# stamp-fixed-mk-4_0.net
KiCad netlist of a schematic drawn in EAGLE
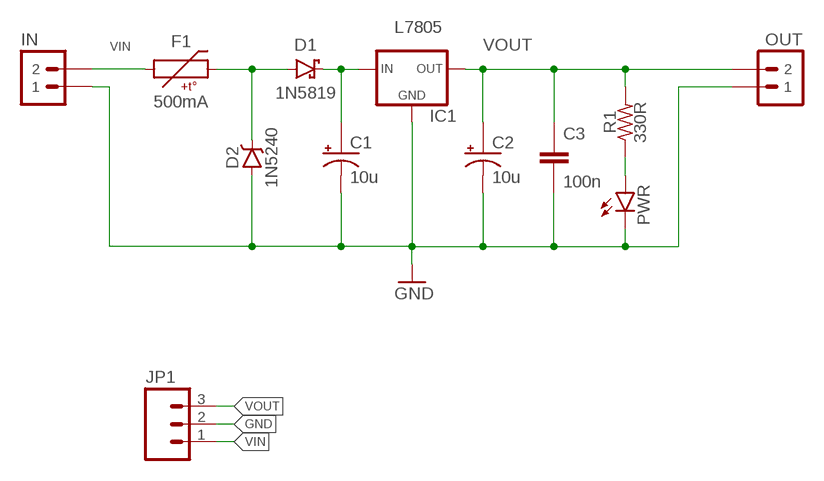
[diagram p0: schematic, sheet 1]

(export (version "E")
  (design (tool "Eeschema 10.0.6"))
  (components
    (comp (ref "C1")
      (value "10u")
      (footprint "eagle-import:E2,5-5")
      (libsource (lib "eagle-import") (part "CAPACITOR-POLARIZEDE2.5-5"))
    )
    (comp (ref "C2")
      (value "10u")
      (footprint "eagle-import:E2,5-5")
      (libsource (lib "eagle-import") (part "CAPACITOR-POLARIZEDE2.5-5"))
    )
    (comp (ref "C3")
      (value "100n")
      (footprint "eagle-import:C025-024X044")
      (libsource (lib "eagle-import") (part "CAPACITOR-CERAMIC025-024X044"))
    )
    (comp (ref "D1")
      (value "1N5819")
      (footprint "eagle-import:DIODE-SCHOTTKY-10.16MM")
      (libsource (lib "eagle-import") (part "DIODE-SCHOTTKYPTH-10.16MM"))
    )
    (comp (ref "D2")
      (value "1N5240")
      (footprint "eagle-import:DIODE-ZENNER-10.16MM")
      (libsource (lib "eagle-import") (part "DIODE-ZENER10.16MM-PTH"))
    )
    (comp (ref "F1")
      (value "500mA")
      (footprint "eagle-import:PTC-PTH-5.08MM")
      (libsource (lib "eagle-import") (part "PTCPTH-5.08MM"))
    )
    (comp (ref "IC1")
      (value "L7805")
      (footprint "eagle-import:TO220-IGO-THERMPAD")
      (libsource (lib "eagle-import") (part "V_REG_78XXTO-220-THERMPAD"))
    )
    (comp (ref "IN")
      (value "M02PTH-CENTERED-R+")
      (footprint "eagle-import:1X02-CENTER-R+")
      (libsource (lib "eagle-import") (part "M02PTH-CENTERED-R+"))
    )
    (comp (ref "JP1")
      (value "M03PTH-CENTERED")
      (footprint "eagle-import:1X03-CENTERED")
      (libsource (lib "eagle-import") (part "M03PTH-CENTERED"))
    )
    (comp (ref "OUT")
      (value "M02PTH-CENTERED-R+")
      (footprint "eagle-import:1X02-CENTER-R+")
      (libsource (lib "eagle-import") (part "M02PTH-CENTERED-R+"))
    )
    (comp (ref "PWR")
      (value "LED3MM-LESS")
      (footprint "eagle-import:LED3MM-LESSSILK")
      (libsource (lib "eagle-import") (part "LED3MM-LESS"))
    )
    (comp (ref "R1")
      (value "330R")
      (footprint "eagle-import:RESISTOR-AXIAL-PTH-5.08MM")
      (libsource (lib "eagle-import") (part "RESISTORPTH-AXIAL-5.08MM"))
    )
  )
  (nets
    (net (code "1") (name "GND") (class "Default")
      (node (ref "C1") (pin "-") (pinfunction "-_-") (pintype "passive"))
      (node (ref "C2") (pin "-") (pinfunction "-_-") (pintype "passive"))
      (node (ref "C3") (pin "2") (pinfunction "2_2") (pintype "passive"))
      (node (ref "D2") (pin "A") (pinfunction "A_A") (pintype "passive"))
      (node (ref "IC1") (pin "4") (pinfunction "GND_4") (pintype "bidirectional"))
      (node (ref "IC1") (pin "GND") (pinfunction "GND_GND") (pintype "bidirectional"))
      (node (ref "IN") (pin "1") (pinfunction "1_1") (pintype "passive"))
      (node (ref "JP1") (pin "2") (pinfunction "2_2") (pintype "passive"))
      (node (ref "OUT") (pin "1") (pinfunction "1_1") (pintype "passive"))
      (node (ref "PWR") (pin "K") (pinfunction "C_K") (pintype "passive"))
    )
    (net (code "2") (name "Net-(C1-Pad+)") (class "Default")
      (node (ref "C1") (pin "+") (pinfunction "+_+") (pintype "passive"))
      (node (ref "D1") (pin "C") (pinfunction "C_C") (pintype "passive"))
      (node (ref "IC1") (pin "IN") (pinfunction "IN_IN") (pintype "bidirectional"))
    )
    (net (code "3") (name "Net-(D2-C)") (class "Default")
      (node (ref "D1") (pin "A") (pinfunction "A_A") (pintype "passive"))
      (node (ref "D2") (pin "K") (pinfunction "C_K") (pintype "passive"))
      (node (ref "F1") (pin "P$2") (pinfunction "2_P$2") (pintype "passive"))
    )
    (net (code "4") (name "Net-(R1-1)") (class "Default")
      (node (ref "PWR") (pin "A") (pinfunction "A_A") (pintype "passive"))
      (node (ref "R1") (pin "P$1") (pinfunction "1_P$1") (pintype "passive"))
    )
    (net (code "5") (name "VIN") (class "Default")
      (node (ref "F1") (pin "P$1") (pinfunction "1_P$1") (pintype "passive"))
      (node (ref "IN") (pin "2") (pinfunction "2_2") (pintype "passive"))
      (node (ref "JP1") (pin "1") (pinfunction "1_1") (pintype "passive"))
    )
    (net (code "6") (name "VOUT") (class "Default")
      (node (ref "C2") (pin "+") (pinfunction "+_+") (pintype "passive"))
      (node (ref "C3") (pin "1") (pinfunction "1_1") (pintype "passive"))
      (node (ref "IC1") (pin "OUT") (pinfunction "OUT_OUT") (pintype "bidirectional"))
      (node (ref "JP1") (pin "3") (pinfunction "3_3") (pintype "passive"))
      (node (ref "OUT") (pin "2") (pinfunction "2_2") (pintype "passive"))
      (node (ref "R1") (pin "P$2") (pinfunction "2_P$2") (pintype "passive"))
    )
  )
)
